# fesztriplazo.net
KiCad netlist of a schematic drawn in EAGLE
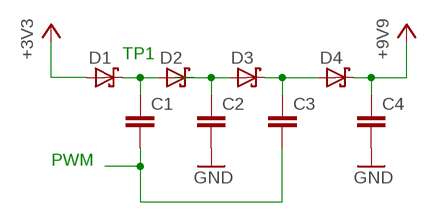
[diagram p0: schematic, sheet 1]

(export (version "E")
  (design (tool "Eeschema 10.0.6"))
  (components
    (comp (ref "C1")
      (value "C-EU050-024X044")
      (footprint "eagle-import:C050-024X044")
      (libsource (lib "eagle-import") (part "C-EU050-024X044"))
    )
    (comp (ref "C2")
      (value "C-EU050-024X044")
      (footprint "eagle-import:C050-024X044")
      (libsource (lib "eagle-import") (part "C-EU050-024X044"))
    )
    (comp (ref "C3")
      (value "C-EU050-024X044")
      (footprint "eagle-import:C050-024X044")
      (libsource (lib "eagle-import") (part "C-EU050-024X044"))
    )
    (comp (ref "C4")
      (value "C-EU050-024X044")
      (footprint "eagle-import:C050-024X044")
      (libsource (lib "eagle-import") (part "C-EU050-024X044"))
    )
    (comp (ref "D1")
      (value "1N5817-B")
      (footprint "eagle-import:DO41-7.6")
      (libsource (lib "eagle-import") (part "1N5817-B"))
    )
    (comp (ref "D2")
      (value "1N5817-B")
      (footprint "eagle-import:DO41-7.6")
      (libsource (lib "eagle-import") (part "1N5817-B"))
    )
    (comp (ref "D3")
      (value "1N5817-B")
      (footprint "eagle-import:DO41-7.6")
      (libsource (lib "eagle-import") (part "1N5817-B"))
    )
    (comp (ref "D4")
      (value "1N5817-B")
      (footprint "eagle-import:DO41-7.6")
      (libsource (lib "eagle-import") (part "1N5817-B"))
    )
  )
  (nets
    (net (code "1") (name "+3V3") (class "Default")
      (node (ref "D1") (pin "A") (pinfunction "A_A") (pintype "passive"))
    )
    (net (code "2") (name "+9V9") (class "Default")
      (node (ref "C4") (pin "1") (pinfunction "1_1") (pintype "passive"))
      (node (ref "D4") (pin "C") (pinfunction "C_C") (pintype "passive"))
    )
    (net (code "3") (name "GND") (class "Default")
      (node (ref "C2") (pin "2") (pinfunction "2_2") (pintype "passive"))
      (node (ref "C4") (pin "2") (pinfunction "2_2") (pintype "passive"))
    )
    (net (code "4") (name "Net-(C1-Pad1)") (class "Default")
      (node (ref "C1") (pin "1") (pinfunction "1_1") (pintype "passive"))
      (node (ref "D1") (pin "C") (pinfunction "C_C") (pintype "passive"))
      (node (ref "D2") (pin "A") (pinfunction "A_A") (pintype "passive"))
    )
    (net (code "5") (name "Net-(C1-Pad2)") (class "Default")
      (node (ref "C1") (pin "2") (pinfunction "2_2") (pintype "passive"))
      (node (ref "C3") (pin "2") (pinfunction "2_2") (pintype "passive"))
    )
    (net (code "6") (name "Net-(C2-Pad1)") (class "Default")
      (node (ref "C2") (pin "1") (pinfunction "1_1") (pintype "passive"))
      (node (ref "D2") (pin "C") (pinfunction "C_C") (pintype "passive"))
      (node (ref "D3") (pin "A") (pinfunction "A_A") (pintype "passive"))
    )
    (net (code "7") (name "Net-(C3-Pad1)") (class "Default")
      (node (ref "C3") (pin "1") (pinfunction "1_1") (pintype "passive"))
      (node (ref "D3") (pin "C") (pinfunction "C_C") (pintype "passive"))
      (node (ref "D4") (pin "A") (pinfunction "A_A") (pintype "passive"))
    )
  )
)
